# power.net
KiCad netlist of a schematic drawn in Altium Designer
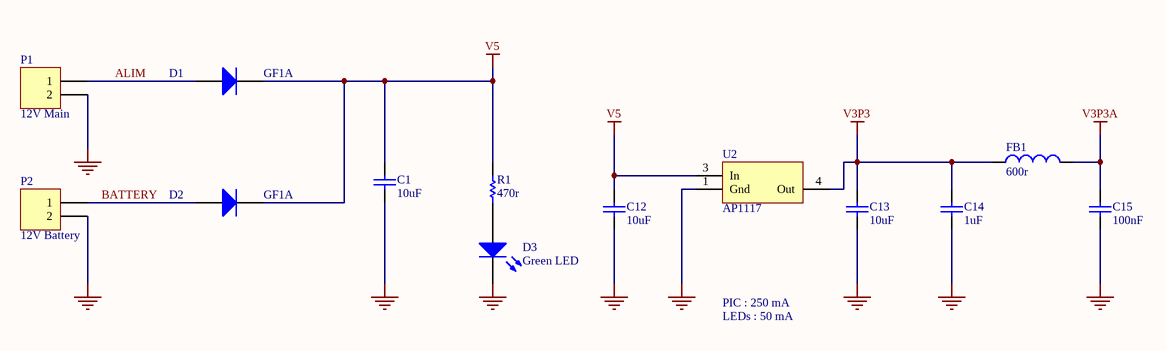
[diagram p0: power.SchDoc]

(export (version "E")
  (design (tool "Eeschema 10.0.6"))
  (components
    (comp (ref "C1")
      (value "10uF")
      (footprint "CAPC2012N")
      (description "Capacitor")
      (fields (field (name "PUBLISHER") "Altium Limited"))
      (libsource (lib "Miscellaneous Devices") (part "Cap"))
    )
    (comp (ref "C12")
      (value "10uF")
      (footprint "CAPC2012N")
      (description "Capacitor")
      (fields (field (name "PUBLISHER") "Altium Limited"))
      (libsource (lib "Miscellaneous Devices") (part "Cap"))
    )
    (comp (ref "C13")
      (value "10uF")
      (footprint "CAPC2012N")
      (description "Capacitor")
      (fields (field (name "PUBLISHER") "Altium Limited"))
      (libsource (lib "Miscellaneous Devices") (part "Cap"))
    )
    (comp (ref "C14")
      (value "1uF")
      (footprint "CAPC1608N")
      (description "Capacitor")
      (fields (field (name "PUBLISHER") "Altium Limited"))
      (libsource (lib "Miscellaneous Devices") (part "Cap"))
    )
    (comp (ref "C15")
      (value "100nF")
      (footprint "CAPC1608N")
      (description "Capacitor")
      (fields (field (name "PUBLISHER") "Altium Limited"))
      (libsource (lib "Miscellaneous Devices") (part "Cap"))
    )
    (comp (ref "D1")
      (value "GF1A")
      (footprint "SMA/DO-214AC_21")
      (description "Default Diode")
      (fields (field (name "PUBLISHER") "Altium Limited"))
      (libsource (lib "Miscellaneous Devices") (part "Diode"))
    )
    (comp (ref "D2")
      (value "GF1A")
      (footprint "SMA/DO-214AC_21")
      (description "Default Diode")
      (fields (field (name "PUBLISHER") "Altium Limited"))
      (libsource (lib "Miscellaneous Devices") (part "Diode"))
    )
    (comp (ref "D3")
      (value "Green LED")
      (footprint "LED 0805")
      (description "Typical RED, GREEN, YELLOW, AMBER GaAs LED")
      (fields (field (name "PUBLISHER") "Altium Limited"))
      (libsource (lib "Miscellaneous Devices") (part "LED2"))
    )
    (comp (ref "FB1")
      (value "600r")
      (footprint "INDC1608AN")
      (description "Inductor")
      (fields (field (name "PUBLISHER") "Altium Limited"))
      (libsource (lib "Miscellaneous Devices") (part "Inductor"))
    )
    (comp (ref "P1")
      (value "12V Main")
      (footprint "PHOENIX_1985195")
      (description "Header, 2-Pin")
      (fields (field (name "PUBLISHER") "Altium Limited"))
      (libsource (lib "Miscellaneous Connectors") (part "Header 2"))
    )
    (comp (ref "P2")
      (value "12V Battery")
      (footprint "PHOENIX_1985195")
      (description "Header, 2-Pin")
      (fields (field (name "PUBLISHER") "Altium Limited"))
      (libsource (lib "Miscellaneous Connectors") (part "Header 2"))
    )
    (comp (ref "R1")
      (value "470r")
      (footprint "RESC1608N")
      (description "Resistor")
      (fields (field (name "PUBLISHER") "Altium Limited"))
      (libsource (lib "Miscellaneous Devices") (part "Res1"))
    )
    (comp (ref "U2")
      (value "AP1117")
      (footprint "TD03B_N")
      (description "1A LDO, 18V input, DPAK")
      (libsource (lib "TP2") (part "AP1117"))
    )
  )
  (nets
    (net (code "1") (name "/ALIM") (class "Default")
      (node (ref "D1") (pin "1") (pinfunction "A_1") (pintype "passive"))
      (node (ref "P1") (pin "1") (pinfunction "1_1") (pintype "passive"))
    )
    (net (code "2") (name "/BATTERY") (class "Default")
      (node (ref "D2") (pin "1") (pinfunction "A_1") (pintype "passive"))
      (node (ref "P2") (pin "1") (pinfunction "1_1") (pintype "passive"))
    )
    (net (code "3") (name "GND") (class "Default")
      (node (ref "C1") (pin "1") (pinfunction "1_1") (pintype "passive"))
      (node (ref "C12") (pin "1") (pinfunction "1_1") (pintype "passive"))
      (node (ref "C13") (pin "1") (pinfunction "1_1") (pintype "passive"))
      (node (ref "C14") (pin "1") (pinfunction "1_1") (pintype "passive"))
      (node (ref "C15") (pin "1") (pinfunction "1_1") (pintype "passive"))
      (node (ref "D3") (pin "2") (pinfunction "K_2") (pintype "passive"))
      (node (ref "P1") (pin "2") (pinfunction "2_2") (pintype "passive"))
      (node (ref "P2") (pin "2") (pinfunction "2_2") (pintype "passive"))
      (node (ref "U2") (pin "1") (pinfunction "Gnd_1") (pintype "passive"))
    )
    (net (code "4") (name "Net-(D3-A)") (class "Default")
      (node (ref "D3") (pin "1") (pinfunction "A_1") (pintype "passive"))
      (node (ref "R1") (pin "1") (pinfunction "1_1") (pintype "passive"))
    )
    (net (code "5") (name "V3P3") (class "Default")
      (node (ref "C13") (pin "2") (pinfunction "2_2") (pintype "passive"))
      (node (ref "C14") (pin "2") (pinfunction "2_2") (pintype "passive"))
      (node (ref "FB1") (pin "1") (pinfunction "1_1") (pintype "passive"))
      (node (ref "U2") (pin "4") (pinfunction "Out_4") (pintype "passive"))
    )
    (net (code "6") (name "V3P3A") (class "Default")
      (node (ref "C15") (pin "2") (pinfunction "2_2") (pintype "passive"))
      (node (ref "FB1") (pin "2") (pinfunction "2_2") (pintype "passive"))
    )
    (net (code "7") (name "V5") (class "Default")
      (node (ref "C1") (pin "2") (pinfunction "2_2") (pintype "passive"))
      (node (ref "C12") (pin "2") (pinfunction "2_2") (pintype "passive"))
      (node (ref "D1") (pin "2") (pinfunction "K_2") (pintype "passive"))
      (node (ref "D2") (pin "2") (pinfunction "K_2") (pintype "passive"))
      (node (ref "R1") (pin "2") (pinfunction "2_2") (pintype "passive"))
      (node (ref "U2") (pin "3") (pinfunction "In_3") (pintype "passive"))
    )
  )
)
